# VGA_Breakout.net
KiCad netlist of a schematic drawn in Altium Designer
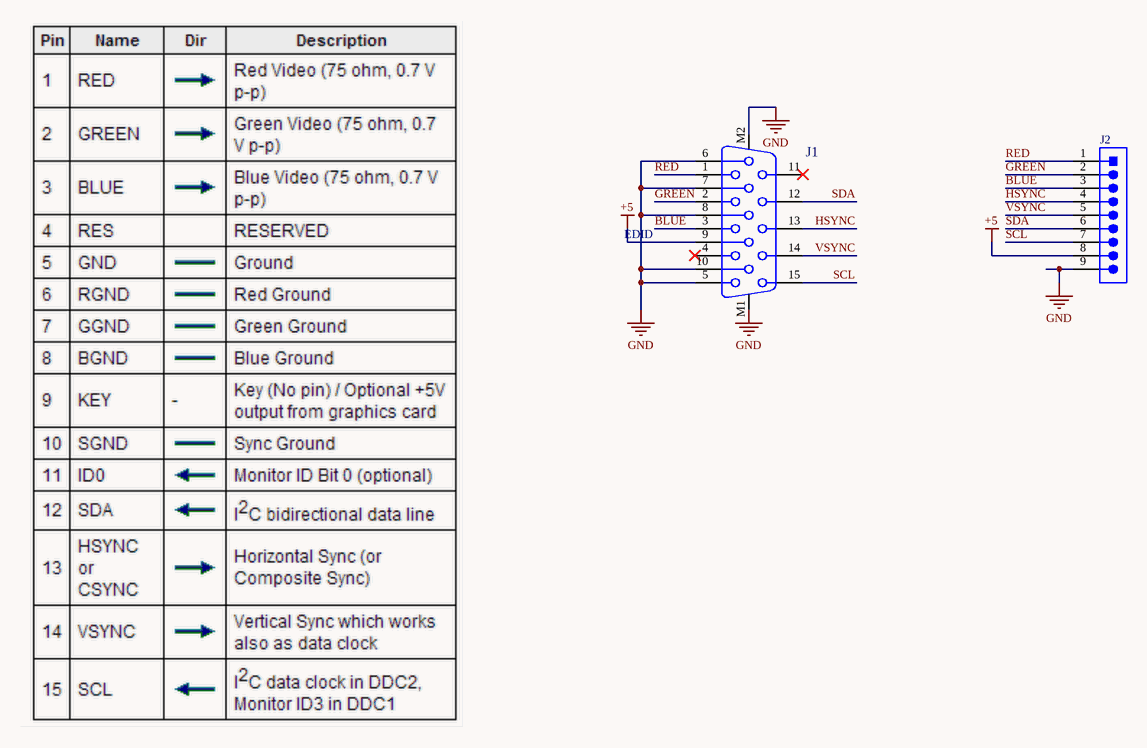
[diagram p0: VGA Breakout.SchDoc]

(export (version "E")
  (design (tool "Eeschema 10.0.6"))
  (components
    (comp (ref "J1")
      (value "DSUB HD DB15 HD14 FEMALE")
      (footprint "618015330923")
      (description "15 Position D-Sub, High Density Receptacle, Female Sockets Connector")
      (fields (field (name "MANUFACTURER") "Würth Elektronik"))
      (libsource (lib "Connectors") (part "DB15F_HD"))
    )
    (comp (ref "J2")
      (value "9 contacts Male header")
      (footprint "PH1-09-UA")
      (description "Connector Male Header 1X9 vertical 9contacts 0.100in pitch Gold")
      (fields (field (name "MANUFACTURER") "Adam Tech"))
      (libsource (lib "Connectors") (part "Header 1X9"))
    )
  )
  (nets
    (net (code "1") (name "+5") (class "Default")
      (node (ref "J1") (pin "9") (pinfunction "9_9") (pintype "passive"))
      (node (ref "J2") (pin "8") (pinfunction "8_8") (pintype "passive"))
    )
    (net (code "2") (name "/BLUE") (class "Default")
      (node (ref "J1") (pin "3") (pinfunction "3_3") (pintype "passive"))
      (node (ref "J2") (pin "3") (pinfunction "3_3") (pintype "passive"))
    )
    (net (code "3") (name "/GREEN") (class "Default")
      (node (ref "J1") (pin "2") (pinfunction "2_2") (pintype "passive"))
      (node (ref "J2") (pin "2") (pinfunction "2_2") (pintype "passive"))
    )
    (net (code "4") (name "/HSYNC") (class "Default")
      (node (ref "J1") (pin "13") (pinfunction "13_13") (pintype "passive"))
      (node (ref "J2") (pin "4") (pinfunction "4_4") (pintype "passive"))
    )
    (net (code "5") (name "/RED") (class "Default")
      (node (ref "J1") (pin "1") (pinfunction "1_1") (pintype "passive"))
      (node (ref "J2") (pin "1") (pinfunction "1_1") (pintype "passive"))
    )
    (net (code "6") (name "/SCL") (class "Default")
      (node (ref "J1") (pin "15") (pinfunction "15_15") (pintype "passive"))
      (node (ref "J2") (pin "7") (pinfunction "7_7") (pintype "passive"))
    )
    (net (code "7") (name "/SDA") (class "Default")
      (node (ref "J1") (pin "12") (pinfunction "12_12") (pintype "passive"))
      (node (ref "J2") (pin "6") (pinfunction "6_6") (pintype "passive"))
    )
    (net (code "8") (name "/VSYNC") (class "Default")
      (node (ref "J1") (pin "14") (pinfunction "14_14") (pintype "passive"))
      (node (ref "J2") (pin "5") (pinfunction "5_5") (pintype "passive"))
    )
    (net (code "9") (name "GND") (class "Default")
      (node (ref "J1") (pin "10") (pinfunction "10_10") (pintype "passive"))
      (node (ref "J1") (pin "5") (pinfunction "5_5") (pintype "passive"))
      (node (ref "J1") (pin "6") (pinfunction "6_6") (pintype "passive"))
      (node (ref "J1") (pin "7") (pinfunction "7_7") (pintype "passive"))
      (node (ref "J1") (pin "8") (pinfunction "8_8") (pintype "passive"))
      (node (ref "J1") (pin "M1") (pinfunction "M1_M1") (pintype "passive"))
      (node (ref "J1") (pin "M2") (pinfunction "M2_M2") (pintype "passive"))
      (node (ref "J2") (pin "9") (pinfunction "9_9") (pintype "passive"))
    )
    (net (code "10") (name "unconnected-(J1-Pad4)") (class "Default")
      (node (ref "J1") (pin "4") (pinfunction "4_4") (pintype "passive+no_connect"))
    )
    (net (code "11") (name "unconnected-(J1-Pad11)") (class "Default")
      (node (ref "J1") (pin "11") (pinfunction "11_11") (pintype "passive+no_connect"))
    )
  )
)
